# Alice3.net
KiCad netlist of a schematic drawn in EAGLE
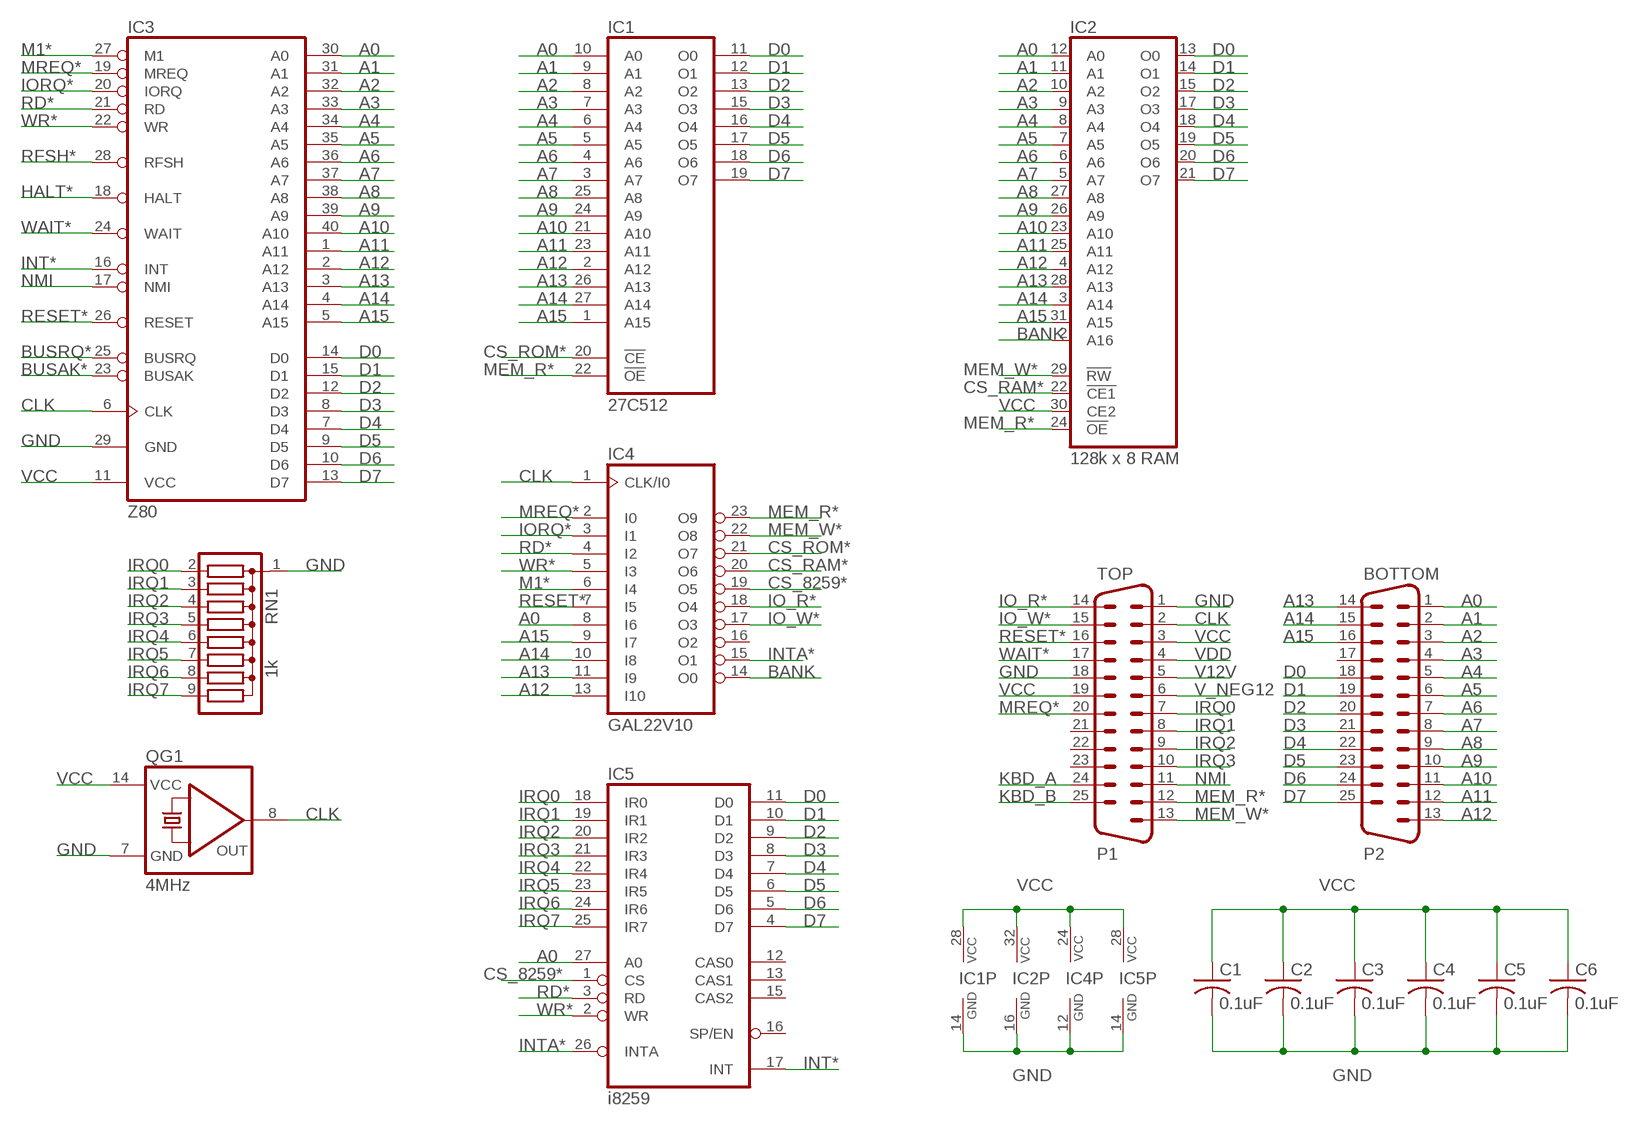
[diagram p0: schematic, sheet 1]

(export (version "E")
  (design (tool "Eeschema 10.0.6"))
  (components
    (comp (ref "BOTTOM")
      (value "P2")
      (footprint "eagle-import:M25HP")
      (libsource (lib "eagle-import") (part "DB25HP"))
    )
    (comp (ref "C1")
      (value "0.1uF")
      (footprint "eagle-import:C1206")
      (libsource (lib "eagle-import") (part "C-USC1206"))
    )
    (comp (ref "C2")
      (value "0.1uF")
      (footprint "eagle-import:C1206")
      (libsource (lib "eagle-import") (part "C-USC1206"))
    )
    (comp (ref "C3")
      (value "0.1uF")
      (footprint "eagle-import:C1206")
      (libsource (lib "eagle-import") (part "C-USC1206"))
    )
    (comp (ref "C4")
      (value "0.1uF")
      (footprint "eagle-import:C1206")
      (libsource (lib "eagle-import") (part "C-USC1206"))
    )
    (comp (ref "C5")
      (value "0.1uF")
      (footprint "eagle-import:C1206")
      (libsource (lib "eagle-import") (part "C-USC1206"))
    )
    (comp (ref "C6")
      (value "0.1uF")
      (footprint "eagle-import:C1206")
      (libsource (lib "eagle-import") (part "C-USC1206"))
    )
    (comp (ref "IC1")
      (value "27C512")
      (footprint "eagle-import:DIL28")
      (libsource (lib "eagle-import") (part "27512"))
    )
    (comp (ref "IC2")
      (value "128k x 8 RAM")
      (footprint "eagle-import:DIL32")
      (libsource (lib "eagle-import") (part "TC551001CP"))
    )
    (comp (ref "IC3")
      (value "Z80")
      (footprint "eagle-import:DIL40")
      (libsource (lib "eagle-import") (part "Z80CPU"))
    )
    (comp (ref "IC4")
      (value "GAL22V10")
      (footprint "eagle-import:DIL24-3")
      (fields (field (name "MPN") "GAL22V10D-7LPN"))
      (libsource (lib "eagle-import") (part "22V10"))
    )
    (comp (ref "IC5")
      (value "i8259")
      (footprint "eagle-import:DIL28-6")
      (libsource (lib "eagle-import") (part "8259A"))
    )
    (comp (ref "QG1")
      (value "4MHz")
      (footprint "eagle-import:DIL14S")
      (libsource (lib "eagle-import") (part "QG5860"))
    )
    (comp (ref "RN1")
      (value "1k")
      (footprint "eagle-import:SIL9")
      (libsource (lib "eagle-import") (part "G08R"))
    )
    (comp (ref "TOP")
      (value "P1")
      (footprint "eagle-import:M25HP")
      (libsource (lib "eagle-import") (part "DB25HP"))
    )
  )
  (nets
    (net (code "1") (name "/A0") (class "Default")
      (node (ref "BOTTOM") (pin "1") (pinfunction "1_1") (pintype "passive"))
      (node (ref "IC1") (pin "10") (pinfunction "A0_10") (pintype "input"))
      (node (ref "IC2") (pin "12") (pinfunction "A0_12") (pintype "input"))
      (node (ref "IC3") (pin "30") (pinfunction "A0_30") (pintype "output"))
      (node (ref "IC4") (pin "8") (pinfunction "I6_8") (pintype "input"))
      (node (ref "IC5") (pin "27") (pinfunction "A0_27") (pintype "input"))
    )
    (net (code "2") (name "/A1") (class "Default")
      (node (ref "BOTTOM") (pin "2") (pinfunction "2_2") (pintype "passive"))
      (node (ref "IC1") (pin "9") (pinfunction "A1_9") (pintype "input"))
      (node (ref "IC2") (pin "11") (pinfunction "A1_11") (pintype "input"))
      (node (ref "IC3") (pin "31") (pinfunction "A1_31") (pintype "output"))
    )
    (net (code "3") (name "/A2") (class "Default")
      (node (ref "BOTTOM") (pin "3") (pinfunction "3_3") (pintype "passive"))
      (node (ref "IC1") (pin "8") (pinfunction "A2_8") (pintype "input"))
      (node (ref "IC2") (pin "10") (pinfunction "A2_10") (pintype "input"))
      (node (ref "IC3") (pin "32") (pinfunction "A2_32") (pintype "output"))
    )
    (net (code "4") (name "/A3") (class "Default")
      (node (ref "BOTTOM") (pin "4") (pinfunction "4_4") (pintype "passive"))
      (node (ref "IC1") (pin "7") (pinfunction "A3_7") (pintype "input"))
      (node (ref "IC2") (pin "9") (pinfunction "A3_9") (pintype "input"))
      (node (ref "IC3") (pin "33") (pinfunction "A3_33") (pintype "output"))
    )
    (net (code "5") (name "/A4") (class "Default")
      (node (ref "BOTTOM") (pin "5") (pinfunction "5_5") (pintype "passive"))
      (node (ref "IC1") (pin "6") (pinfunction "A4_6") (pintype "input"))
      (node (ref "IC2") (pin "8") (pinfunction "A4_8") (pintype "input"))
      (node (ref "IC3") (pin "34") (pinfunction "A4_34") (pintype "output"))
    )
    (net (code "6") (name "/A5") (class "Default")
      (node (ref "BOTTOM") (pin "6") (pinfunction "6_6") (pintype "passive"))
      (node (ref "IC1") (pin "5") (pinfunction "A5_5") (pintype "input"))
      (node (ref "IC2") (pin "7") (pinfunction "A5_7") (pintype "input"))
      (node (ref "IC3") (pin "35") (pinfunction "A5_35") (pintype "output"))
    )
    (net (code "7") (name "/A6") (class "Default")
      (node (ref "BOTTOM") (pin "7") (pinfunction "7_7") (pintype "passive"))
      (node (ref "IC1") (pin "4") (pinfunction "A6_4") (pintype "input"))
      (node (ref "IC2") (pin "6") (pinfunction "A6_6") (pintype "input"))
      (node (ref "IC3") (pin "36") (pinfunction "A6_36") (pintype "output"))
    )
    (net (code "8") (name "/A7") (class "Default")
      (node (ref "BOTTOM") (pin "8") (pinfunction "8_8") (pintype "passive"))
      (node (ref "IC1") (pin "3") (pinfunction "A7_3") (pintype "input"))
      (node (ref "IC2") (pin "5") (pinfunction "A7_5") (pintype "input"))
      (node (ref "IC3") (pin "37") (pinfunction "A7_37") (pintype "output"))
    )
    (net (code "9") (name "/A8") (class "Default")
      (node (ref "BOTTOM") (pin "9") (pinfunction "9_9") (pintype "passive"))
      (node (ref "IC1") (pin "25") (pinfunction "A8_25") (pintype "input"))
      (node (ref "IC2") (pin "27") (pinfunction "A8_27") (pintype "input"))
      (node (ref "IC3") (pin "38") (pinfunction "A8_38") (pintype "output"))
    )
    (net (code "10") (name "/A9") (class "Default")
      (node (ref "BOTTOM") (pin "10") (pinfunction "10_10") (pintype "passive"))
      (node (ref "IC1") (pin "24") (pinfunction "A9_24") (pintype "input"))
      (node (ref "IC2") (pin "26") (pinfunction "A9_26") (pintype "input"))
      (node (ref "IC3") (pin "39") (pinfunction "A9_39") (pintype "output"))
    )
    (net (code "11") (name "/A10") (class "Default")
      (node (ref "BOTTOM") (pin "11") (pinfunction "11_11") (pintype "passive"))
      (node (ref "IC1") (pin "21") (pinfunction "A10_21") (pintype "input"))
      (node (ref "IC2") (pin "23") (pinfunction "A10_23") (pintype "input"))
      (node (ref "IC3") (pin "40") (pinfunction "A10_40") (pintype "output"))
    )
    (net (code "12") (name "/A11") (class "Default")
      (node (ref "BOTTOM") (pin "12") (pinfunction "12_12") (pintype "passive"))
      (node (ref "IC1") (pin "23") (pinfunction "A11_23") (pintype "input"))
      (node (ref "IC2") (pin "25") (pinfunction "A11_25") (pintype "input"))
      (node (ref "IC3") (pin "1") (pinfunction "A11_1") (pintype "output"))
    )
    (net (code "13") (name "/A12") (class "Default")
      (node (ref "BOTTOM") (pin "13") (pinfunction "13_13") (pintype "passive"))
      (node (ref "IC1") (pin "2") (pinfunction "A12_2") (pintype "input"))
      (node (ref "IC2") (pin "4") (pinfunction "A12_4") (pintype "input"))
      (node (ref "IC3") (pin "2") (pinfunction "A12_2") (pintype "output"))
      (node (ref "IC4") (pin "13") (pinfunction "I10_13") (pintype "input"))
    )
    (net (code "14") (name "/A13") (class "Default")
      (node (ref "BOTTOM") (pin "14") (pinfunction "14_14") (pintype "passive"))
      (node (ref "IC1") (pin "26") (pinfunction "A13_26") (pintype "input"))
      (node (ref "IC2") (pin "28") (pinfunction "A13_28") (pintype "input"))
      (node (ref "IC3") (pin "3") (pinfunction "A13_3") (pintype "output"))
      (node (ref "IC4") (pin "11") (pinfunction "I9_11") (pintype "input"))
    )
    (net (code "15") (name "/A14") (class "Default")
      (node (ref "BOTTOM") (pin "15") (pinfunction "15_15") (pintype "passive"))
      (node (ref "IC1") (pin "27") (pinfunction "A14_27") (pintype "input"))
      (node (ref "IC2") (pin "3") (pinfunction "A14_3") (pintype "input"))
      (node (ref "IC3") (pin "4") (pinfunction "A14_4") (pintype "output"))
      (node (ref "IC4") (pin "10") (pinfunction "I8_10") (pintype "input"))
    )
    (net (code "16") (name "/A15") (class "Default")
      (node (ref "BOTTOM") (pin "16") (pinfunction "16_16") (pintype "passive"))
      (node (ref "IC1") (pin "1") (pinfunction "A15_1") (pintype "input"))
      (node (ref "IC2") (pin "31") (pinfunction "A15_31") (pintype "input"))
      (node (ref "IC3") (pin "5") (pinfunction "A15_5") (pintype "output"))
      (node (ref "IC4") (pin "9") (pinfunction "I7_9") (pintype "input"))
    )
    (net (code "17") (name "/BANK") (class "Default")
      (node (ref "IC2") (pin "2") (pinfunction "A16_2") (pintype "input"))
      (node (ref "IC4") (pin "14") (pinfunction "O0_14") (pintype "bidirectional"))
    )
    (net (code "18") (name "/BUSAK*") (class "Default")
      (node (ref "IC3") (pin "23") (pinfunction "BUSAK_23") (pintype "output"))
    )
    (net (code "19") (name "/BUSRQ*") (class "Default")
      (node (ref "IC3") (pin "25") (pinfunction "BUSRQ_25") (pintype "input"))
    )
    (net (code "20") (name "/CLK") (class "Default")
      (node (ref "IC3") (pin "6") (pinfunction "CLK_6") (pintype "input"))
      (node (ref "IC4") (pin "1") (pinfunction "CLK/I0_1") (pintype "input"))
      (node (ref "QG1") (pin "8") (pinfunction "OUT_8") (pintype "output"))
      (node (ref "TOP") (pin "2") (pinfunction "2_2") (pintype "passive"))
    )
    (net (code "21") (name "/CS_8259*") (class "Default")
      (node (ref "IC4") (pin "19") (pinfunction "O5_19") (pintype "bidirectional"))
      (node (ref "IC5") (pin "1") (pinfunction "CS_1") (pintype "input"))
    )
    (net (code "22") (name "/CS_RAM*") (class "Default")
      (node (ref "IC2") (pin "22") (pinfunction "~{CE1}_22") (pintype "input"))
      (node (ref "IC4") (pin "20") (pinfunction "O6_20") (pintype "bidirectional"))
    )
    (net (code "23") (name "/CS_ROM*") (class "Default")
      (node (ref "IC1") (pin "20") (pinfunction "~{CE}_20") (pintype "input"))
      (node (ref "IC4") (pin "21") (pinfunction "O7_21") (pintype "bidirectional"))
    )
    (net (code "24") (name "/D0") (class "Default")
      (node (ref "BOTTOM") (pin "18") (pinfunction "18_18") (pintype "passive"))
      (node (ref "IC1") (pin "11") (pinfunction "O0_11") (pintype "tri_state"))
      (node (ref "IC2") (pin "13") (pinfunction "O0_13") (pintype "tri_state"))
      (node (ref "IC3") (pin "14") (pinfunction "D0_14") (pintype "bidirectional"))
      (node (ref "IC5") (pin "11") (pinfunction "D0_11") (pintype "bidirectional"))
    )
    (net (code "25") (name "/D1") (class "Default")
      (node (ref "BOTTOM") (pin "19") (pinfunction "19_19") (pintype "passive"))
      (node (ref "IC1") (pin "12") (pinfunction "O1_12") (pintype "tri_state"))
      (node (ref "IC2") (pin "14") (pinfunction "O1_14") (pintype "tri_state"))
      (node (ref "IC3") (pin "15") (pinfunction "D1_15") (pintype "bidirectional"))
      (node (ref "IC5") (pin "10") (pinfunction "D1_10") (pintype "bidirectional"))
    )
    (net (code "26") (name "/D2") (class "Default")
      (node (ref "BOTTOM") (pin "20") (pinfunction "20_20") (pintype "passive"))
      (node (ref "IC1") (pin "13") (pinfunction "O2_13") (pintype "tri_state"))
      (node (ref "IC2") (pin "15") (pinfunction "O2_15") (pintype "tri_state"))
      (node (ref "IC3") (pin "12") (pinfunction "D2_12") (pintype "bidirectional"))
      (node (ref "IC5") (pin "9") (pinfunction "D2_9") (pintype "bidirectional"))
    )
    (net (code "27") (name "/D3") (class "Default")
      (node (ref "BOTTOM") (pin "21") (pinfunction "21_21") (pintype "passive"))
      (node (ref "IC1") (pin "15") (pinfunction "O3_15") (pintype "tri_state"))
      (node (ref "IC2") (pin "17") (pinfunction "O3_17") (pintype "tri_state"))
      (node (ref "IC3") (pin "8") (pinfunction "D3_8") (pintype "bidirectional"))
      (node (ref "IC5") (pin "8") (pinfunction "D3_8") (pintype "bidirectional"))
    )
    (net (code "28") (name "/D4") (class "Default")
      (node (ref "BOTTOM") (pin "22") (pinfunction "22_22") (pintype "passive"))
      (node (ref "IC1") (pin "16") (pinfunction "O4_16") (pintype "tri_state"))
      (node (ref "IC2") (pin "18") (pinfunction "O4_18") (pintype "tri_state"))
      (node (ref "IC3") (pin "7") (pinfunction "D4_7") (pintype "bidirectional"))
      (node (ref "IC5") (pin "7") (pinfunction "D4_7") (pintype "bidirectional"))
    )
    (net (code "29") (name "/D5") (class "Default")
      (node (ref "BOTTOM") (pin "23") (pinfunction "23_23") (pintype "passive"))
      (node (ref "IC1") (pin "17") (pinfunction "O5_17") (pintype "tri_state"))
      (node (ref "IC2") (pin "19") (pinfunction "O5_19") (pintype "tri_state"))
      (node (ref "IC3") (pin "9") (pinfunction "D5_9") (pintype "bidirectional"))
      (node (ref "IC5") (pin "6") (pinfunction "D5_6") (pintype "bidirectional"))
    )
    (net (code "30") (name "/D6") (class "Default")
      (node (ref "BOTTOM") (pin "24") (pinfunction "24_24") (pintype "passive"))
      (node (ref "IC1") (pin "18") (pinfunction "O6_18") (pintype "tri_state"))
      (node (ref "IC2") (pin "20") (pinfunction "O6_20") (pintype "tri_state"))
      (node (ref "IC3") (pin "10") (pinfunction "D6_10") (pintype "bidirectional"))
      (node (ref "IC5") (pin "5") (pinfunction "D6_5") (pintype "bidirectional"))
    )
    (net (code "31") (name "/D7") (class "Default")
      (node (ref "BOTTOM") (pin "25") (pinfunction "25_25") (pintype "passive"))
      (node (ref "IC1") (pin "19") (pinfunction "O7_19") (pintype "tri_state"))
      (node (ref "IC2") (pin "21") (pinfunction "O7_21") (pintype "tri_state"))
      (node (ref "IC3") (pin "13") (pinfunction "D7_13") (pintype "bidirectional"))
      (node (ref "IC5") (pin "4") (pinfunction "D7_4") (pintype "bidirectional"))
    )
    (net (code "32") (name "/GND") (class "Default")
      (node (ref "C1") (pin "2") (pinfunction "2_2") (pintype "passive"))
      (node (ref "C2") (pin "2") (pinfunction "2_2") (pintype "passive"))
      (node (ref "C3") (pin "2") (pinfunction "2_2") (pintype "passive"))
      (node (ref "C4") (pin "2") (pinfunction "2_2") (pintype "passive"))
      (node (ref "C5") (pin "2") (pinfunction "2_2") (pintype "passive"))
      (node (ref "C6") (pin "2") (pinfunction "2_2") (pintype "passive"))
      (node (ref "IC1") (pin "14") (pinfunction "GND_14") (pintype "power_in"))
      (node (ref "IC2") (pin "16") (pinfunction "GND_16") (pintype "power_in"))
      (node (ref "IC3") (pin "29") (pinfunction "GND_29") (pintype "power_in"))
      (node (ref "IC4") (pin "12") (pinfunction "GND_12") (pintype "power_in"))
      (node (ref "IC5") (pin "14") (pinfunction "GND_14") (pintype "power_in"))
      (node (ref "QG1") (pin "7") (pinfunction "GND_7") (pintype "power_in"))
      (node (ref "RN1") (pin "1") (pinfunction "1_1") (pintype "passive"))
      (node (ref "TOP") (pin "1") (pinfunction "1_1") (pintype "passive"))
      (node (ref "TOP") (pin "18") (pinfunction "18_18") (pintype "passive"))
    )
    (net (code "33") (name "/HALT*") (class "Default")
      (node (ref "IC3") (pin "18") (pinfunction "HALT_18") (pintype "output"))
    )
    (net (code "34") (name "/INT*") (class "Default")
      (node (ref "IC3") (pin "16") (pinfunction "INT_16") (pintype "input"))
      (node (ref "IC5") (pin "17") (pinfunction "INT_17") (pintype "output"))
    )
    (net (code "35") (name "/INTA*") (class "Default")
      (node (ref "IC4") (pin "15") (pinfunction "O1_15") (pintype "bidirectional"))
      (node (ref "IC5") (pin "26") (pinfunction "INTA_26") (pintype "input"))
    )
    (net (code "36") (name "/IORQ*") (class "Default")
      (node (ref "IC3") (pin "20") (pinfunction "IORQ_20") (pintype "output"))
      (node (ref "IC4") (pin "3") (pinfunction "I1_3") (pintype "input"))
    )
    (net (code "37") (name "/IO_R*") (class "Default")
      (node (ref "IC4") (pin "18") (pinfunction "O4_18") (pintype "bidirectional"))
      (node (ref "TOP") (pin "14") (pinfunction "14_14") (pintype "passive"))
    )
    (net (code "38") (name "/IO_W*") (class "Default")
      (node (ref "IC4") (pin "17") (pinfunction "O3_17") (pintype "bidirectional"))
      (node (ref "TOP") (pin "15") (pinfunction "15_15") (pintype "passive"))
    )
    (net (code "39") (name "/IRQ0") (class "Default")
      (node (ref "IC5") (pin "18") (pinfunction "IR0_18") (pintype "input"))
      (node (ref "RN1") (pin "2") (pinfunction "2_2") (pintype "passive"))
      (node (ref "TOP") (pin "7") (pinfunction "7_7") (pintype "passive"))
    )
    (net (code "40") (name "/IRQ1") (class "Default")
      (node (ref "IC5") (pin "19") (pinfunction "IR1_19") (pintype "input"))
      (node (ref "RN1") (pin "3") (pinfunction "3_3") (pintype "passive"))
      (node (ref "TOP") (pin "8") (pinfunction "8_8") (pintype "passive"))
    )
    (net (code "41") (name "/IRQ2") (class "Default")
      (node (ref "IC5") (pin "20") (pinfunction "IR2_20") (pintype "input"))
      (node (ref "RN1") (pin "4") (pinfunction "4_4") (pintype "passive"))
      (node (ref "TOP") (pin "9") (pinfunction "9_9") (pintype "passive"))
    )
    (net (code "42") (name "/IRQ3") (class "Default")
      (node (ref "IC5") (pin "21") (pinfunction "IR3_21") (pintype "input"))
      (node (ref "RN1") (pin "5") (pinfunction "5_5") (pintype "passive"))
      (node (ref "TOP") (pin "10") (pinfunction "10_10") (pintype "passive"))
    )
    (net (code "43") (name "/IRQ4") (class "Default")
      (node (ref "IC5") (pin "22") (pinfunction "IR4_22") (pintype "input"))
      (node (ref "RN1") (pin "6") (pinfunction "6_6") (pintype "passive"))
    )
    (net (code "44") (name "/IRQ5") (class "Default")
      (node (ref "IC5") (pin "23") (pinfunction "IR5_23") (pintype "input"))
      (node (ref "RN1") (pin "7") (pinfunction "7_7") (pintype "passive"))
    )
    (net (code "45") (name "/IRQ6") (class "Default")
      (node (ref "IC5") (pin "24") (pinfunction "IR6_24") (pintype "input"))
      (node (ref "RN1") (pin "8") (pinfunction "8_8") (pintype "passive"))
    )
    (net (code "46") (name "/IRQ7") (class "Default")
      (node (ref "IC5") (pin "25") (pinfunction "IR7_25") (pintype "input"))
      (node (ref "RN1") (pin "9") (pinfunction "9_9") (pintype "passive"))
    )
    (net (code "47") (name "/KBD_A") (class "Default")
      (node (ref "TOP") (pin "24") (pinfunction "24_24") (pintype "passive"))
    )
    (net (code "48") (name "/KBD_B") (class "Default")
      (node (ref "TOP") (pin "25") (pinfunction "25_25") (pintype "passive"))
    )
    (net (code "49") (name "/M1*") (class "Default")
      (node (ref "IC3") (pin "27") (pinfunction "M1_27") (pintype "output"))
      (node (ref "IC4") (pin "6") (pinfunction "I4_6") (pintype "input"))
    )
    (net (code "50") (name "/MEM_R*") (class "Default")
      (node (ref "IC1") (pin "22") (pinfunction "~{OE}_22") (pintype "input"))
      (node (ref "IC2") (pin "24") (pinfunction "~{OE}_24") (pintype "input"))
      (node (ref "IC4") (pin "23") (pinfunction "O9_23") (pintype "bidirectional"))
      (node (ref "TOP") (pin "12") (pinfunction "12_12") (pintype "passive"))
    )
    (net (code "51") (name "/MEM_W*") (class "Default")
      (node (ref "IC2") (pin "29") (pinfunction "~{RW}_29") (pintype "input"))
      (node (ref "IC4") (pin "22") (pinfunction "O8_22") (pintype "bidirectional"))
      (node (ref "TOP") (pin "13") (pinfunction "13_13") (pintype "passive"))
    )
    (net (code "52") (name "/MREQ*") (class "Default")
      (node (ref "IC3") (pin "19") (pinfunction "MREQ_19") (pintype "output"))
      (node (ref "IC4") (pin "2") (pinfunction "I0_2") (pintype "input"))
      (node (ref "TOP") (pin "20") (pinfunction "20_20") (pintype "passive"))
    )
    (net (code "53") (name "/NMI") (class "Default")
      (node (ref "IC3") (pin "17") (pinfunction "NMI_17") (pintype "input"))
      (node (ref "TOP") (pin "11") (pinfunction "11_11") (pintype "passive"))
    )
    (net (code "54") (name "/RD*") (class "Default")
      (node (ref "IC3") (pin "21") (pinfunction "RD_21") (pintype "output"))
      (node (ref "IC4") (pin "4") (pinfunction "I2_4") (pintype "input"))
      (node (ref "IC5") (pin "3") (pinfunction "RD_3") (pintype "input"))
    )
    (net (code "55") (name "/RESET*") (class "Default")
      (node (ref "IC3") (pin "26") (pinfunction "RESET_26") (pintype "input"))
      (node (ref "IC4") (pin "7") (pinfunction "I5_7") (pintype "input"))
      (node (ref "TOP") (pin "16") (pinfunction "16_16") (pintype "passive"))
    )
    (net (code "56") (name "/RFSH*") (class "Default")
      (node (ref "IC3") (pin "28") (pinfunction "RFSH_28") (pintype "output"))
    )
    (net (code "57") (name "/V12V") (class "Default")
      (node (ref "TOP") (pin "5") (pinfunction "5_5") (pintype "passive"))
    )
    (net (code "58") (name "/VCC") (class "Default")
      (node (ref "C1") (pin "1") (pinfunction "1_1") (pintype "passive"))
      (node (ref "C2") (pin "1") (pinfunction "1_1") (pintype "passive"))
      (node (ref "C3") (pin "1") (pinfunction "1_1") (pintype "passive"))
      (node (ref "C4") (pin "1") (pinfunction "1_1") (pintype "passive"))
      (node (ref "C5") (pin "1") (pinfunction "1_1") (pintype "passive"))
      (node (ref "C6") (pin "1") (pinfunction "1_1") (pintype "passive"))
      (node (ref "IC1") (pin "28") (pinfunction "VCC_28") (pintype "power_in"))
      (node (ref "IC2") (pin "30") (pinfunction "CE2_30") (pintype "input"))
      (node (ref "IC2") (pin "32") (pinfunction "VCC_32") (pintype "power_in"))
      (node (ref "IC3") (pin "11") (pinfunction "VCC_11") (pintype "power_in"))
      (node (ref "IC4") (pin "24") (pinfunction "VCC_24") (pintype "power_in"))
      (node (ref "IC5") (pin "28") (pinfunction "VCC_28") (pintype "power_in"))
      (node (ref "QG1") (pin "14") (pinfunction "VCC_14") (pintype "power_in"))
      (node (ref "TOP") (pin "19") (pinfunction "19_19") (pintype "passive"))
      (node (ref "TOP") (pin "3") (pinfunction "3_3") (pintype "passive"))
    )
    (net (code "59") (name "/VDD") (class "Default")
      (node (ref "TOP") (pin "4") (pinfunction "4_4") (pintype "passive"))
    )
    (net (code "60") (name "/V_NEG12") (class "Default")
      (node (ref "TOP") (pin "6") (pinfunction "6_6") (pintype "passive"))
    )
    (net (code "61") (name "/WAIT*") (class "Default")
      (node (ref "IC3") (pin "24") (pinfunction "WAIT_24") (pintype "input"))
      (node (ref "TOP") (pin "17") (pinfunction "17_17") (pintype "passive"))
    )
    (net (code "62") (name "/WR*") (class "Default")
      (node (ref "IC3") (pin "22") (pinfunction "WR_22") (pintype "output"))
      (node (ref "IC4") (pin "5") (pinfunction "I3_5") (pintype "input"))
      (node (ref "IC5") (pin "2") (pinfunction "WR_2") (pintype "input"))
    )
    (net (code "63") (name "unconnected-(BOTTOM-Pad17)") (class "Default")
      (node (ref "BOTTOM") (pin "17") (pinfunction "17_17") (pintype "passive"))
    )
    (net (code "64") (name "unconnected-(IC4A-O2-Pad16)") (class "Default")
      (node (ref "IC4") (pin "16") (pinfunction "O2_16") (pintype "bidirectional"))
    )
    (net (code "65") (name "unconnected-(IC5A-CAS0-Pad12)") (class "Default")
      (node (ref "IC5") (pin "12") (pinfunction "CAS0_12") (pintype "bidirectional"))
    )
    (net (code "66") (name "unconnected-(IC5A-CAS1-Pad13)") (class "Default")
      (node (ref "IC5") (pin "13") (pinfunction "CAS1_13") (pintype "bidirectional"))
    )
    (net (code "67") (name "unconnected-(IC5A-CAS2-Pad15)") (class "Default")
      (node (ref "IC5") (pin "15") (pinfunction "CAS2_15") (pintype "bidirectional"))
    )
    (net (code "68") (name "unconnected-(IC5A-SP{slash}EN-Pad16)") (class "Default")
      (node (ref "IC5") (pin "16") (pinfunction "SP/EN_16") (pintype "bidirectional"))
    )
    (net (code "69") (name "unconnected-(TOP-Pad21)") (class "Default")
      (node (ref "TOP") (pin "21") (pinfunction "21_21") (pintype "passive"))
    )
    (net (code "70") (name "unconnected-(TOP-Pad22)") (class "Default")
      (node (ref "TOP") (pin "22") (pinfunction "22_22") (pintype "passive"))
    )
    (net (code "71") (name "unconnected-(TOP-Pad23)") (class "Default")
      (node (ref "TOP") (pin "23") (pinfunction "23_23") (pintype "passive"))
    )
  )
)
